# 3DR-APM25-Power-Module-V10.net
KiCad netlist of a schematic drawn in EAGLE
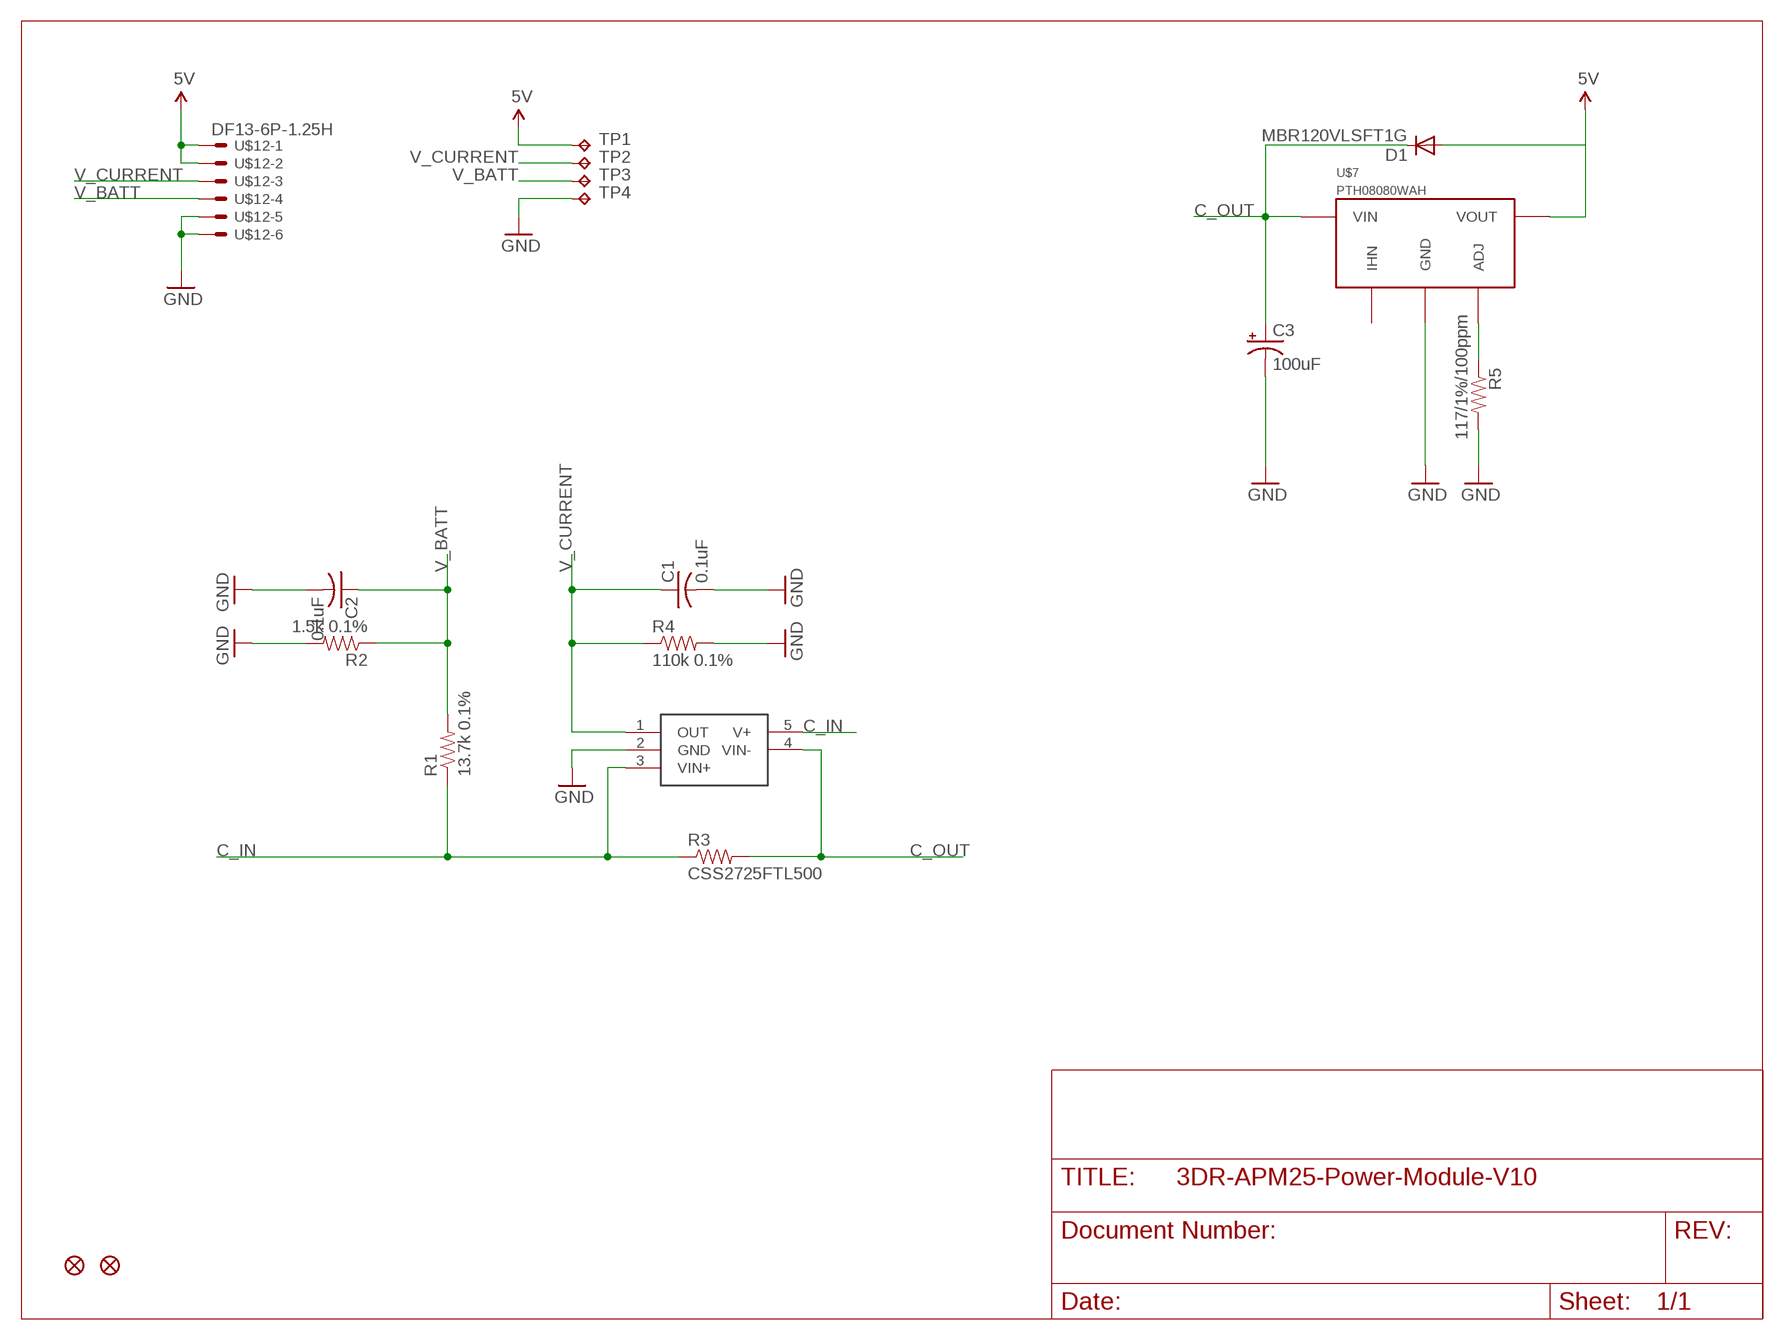
[diagram p0: schematic, sheet 1]

(export (version "E")
  (design (tool "Eeschema 10.0.6"))
  (components
    (comp (ref "C1")
      (value "0.1uF")
      (footprint "eagle-import:C0402")
      (libsource (lib "eagle-import") (part "C-USC0402"))
    )
    (comp (ref "C2")
      (value "0.1uF")
      (footprint "eagle-import:C0402")
      (libsource (lib "eagle-import") (part "C-USC0402"))
    )
    (comp (ref "C3")
      (value "100uF")
      (footprint "eagle-import:EIA7343")
      (libsource (lib "eagle-import") (part "CAP_POL7343"))
    )
    (comp (ref "D1")
      (value "MBR120VLSFT1G")
      (footprint "eagle-import:SOD-123-DIO")
      (libsource (lib "eagle-import") (part "DIODE-SOD-123"))
    )
    (comp (ref "JP1")
      (value "FIDUCIAL1X2")
      (footprint "eagle-import:FIDUCIAL-1X2")
      (libsource (lib "eagle-import") (part "FIDUCIAL1X2"))
    )
    (comp (ref "JP2")
      (value "FIDUCIAL1X2")
      (footprint "eagle-import:FIDUCIAL-1X2")
      (libsource (lib "eagle-import") (part "FIDUCIAL1X2"))
    )
    (comp (ref "R1")
      (value "13.7k 0.1%")
      (footprint "eagle-import:0402-RES")
      (libsource (lib "eagle-import") (part "RESISTOR0402-RES"))
    )
    (comp (ref "R2")
      (value "1.5k 0.1%")
      (footprint "eagle-import:0402-RES")
      (libsource (lib "eagle-import") (part "RESISTOR0402-RES"))
    )
    (comp (ref "R3")
      (value "CSS2725FTL500")
      (footprint "eagle-import:2725-RES")
      (libsource (lib "eagle-import") (part "CSS2725FTL250"))
    )
    (comp (ref "R4")
      (value "110k 0.1%")
      (footprint "eagle-import:0402-RES")
      (libsource (lib "eagle-import") (part "RESISTOR0402-RES"))
    )
    (comp (ref "R5")
      (value "117/1%/100ppm")
      (footprint "eagle-import:0402-RES")
      (libsource (lib "eagle-import") (part "RESISTOR0402-RES"))
    )
    (comp (ref "TP1")
      (value "TPTP19SQ")
      (footprint "eagle-import:TP19SQ")
      (libsource (lib "eagle-import") (part "TPTP19SQ"))
    )
    (comp (ref "TP2")
      (value "TPTP19SQ")
      (footprint "eagle-import:TP19SQ")
      (libsource (lib "eagle-import") (part "TPTP19SQ"))
    )
    (comp (ref "TP3")
      (value "TPTP19SQ")
      (footprint "eagle-import:TP19SQ")
      (libsource (lib "eagle-import") (part "TPTP19SQ"))
    )
    (comp (ref "TP4")
      (value "TPTP19SQ")
      (footprint "eagle-import:TP19SQ")
      (libsource (lib "eagle-import") (part "TPTP19SQ"))
    )
    (comp (ref "U$2")
      (value "INA169")
      (footprint "eagle-import:SOT23-5")
      (libsource (lib "eagle-import") (part "INA169"))
    )
    (comp (ref "U$7")
      (value "PTH08080WAH")
      (footprint "eagle-import:PTH08080W_TH")
      (libsource (lib "eagle-import") (part "PTH08080WAH"))
    )
    (comp (ref "U$12")
      (value "DF13-6P-1.25H")
      (footprint "eagle-import:DF13A-6P-1.25H")
      (libsource (lib "eagle-import") (part "DF13-6P-1.25?H"))
    )
  )
  (nets
    (net (code "1") (name "/C_IN") (class "Default")
      (node (ref "R1") (pin "1") (pinfunction "1_1") (pintype "passive"))
      (node (ref "R3") (pin "P$1") (pinfunction "1_P$1") (pintype "passive"))
      (node (ref "U$2") (pin "3") (pinfunction "VIN+_3") (pintype "bidirectional"))
      (node (ref "U$2") (pin "5") (pinfunction "V+_5") (pintype "bidirectional"))
    )
    (net (code "2") (name "/C_OUT") (class "Default")
      (node (ref "C3") (pin "A") (pinfunction "+_A") (pintype "passive"))
      (node (ref "D1") (pin "C") (pinfunction "C_C") (pintype "passive"))
      (node (ref "R3") (pin "P$2") (pinfunction "2_P$2") (pintype "passive"))
      (node (ref "U$2") (pin "4") (pinfunction "VIN-_4") (pintype "bidirectional"))
      (node (ref "U$7") (pin "1") (pinfunction "VIN_1") (pintype "power_in"))
    )
    (net (code "3") (name "/V_BATT") (class "Default")
      (node (ref "C2") (pin "1") (pinfunction "1_1") (pintype "passive"))
      (node (ref "R1") (pin "2") (pinfunction "2_2") (pintype "passive"))
      (node (ref "R2") (pin "1") (pinfunction "1_1") (pintype "passive"))
      (node (ref "TP3") (pin "TP") (pinfunction "TP_TP") (pintype "input"))
      (node (ref "U$12") (pin "4") (pinfunction "S_4") (pintype "passive"))
    )
    (net (code "4") (name "/V_CURRENT") (class "Default")
      (node (ref "C1") (pin "1") (pinfunction "1_1") (pintype "passive"))
      (node (ref "R4") (pin "1") (pinfunction "1_1") (pintype "passive"))
      (node (ref "TP2") (pin "TP") (pinfunction "TP_TP") (pintype "input"))
      (node (ref "U$12") (pin "3") (pinfunction "S_3") (pintype "passive"))
      (node (ref "U$2") (pin "1") (pinfunction "OUT_1") (pintype "bidirectional"))
    )
    (net (code "5") (name "5V") (class "Default")
      (node (ref "D1") (pin "A") (pinfunction "A_A") (pintype "passive"))
      (node (ref "TP1") (pin "TP") (pinfunction "TP_TP") (pintype "input"))
      (node (ref "U$12") (pin "1") (pinfunction "S_1") (pintype "passive"))
      (node (ref "U$12") (pin "2") (pinfunction "S_2") (pintype "passive"))
      (node (ref "U$7") (pin "3") (pinfunction "VOUT_3") (pintype "power_in"))
    )
    (net (code "6") (name "GND") (class "Default")
      (node (ref "C1") (pin "2") (pinfunction "2_2") (pintype "passive"))
      (node (ref "C2") (pin "2") (pinfunction "2_2") (pintype "passive"))
      (node (ref "C3") (pin "C") (pinfunction "-_C") (pintype "passive"))
      (node (ref "R2") (pin "2") (pinfunction "2_2") (pintype "passive"))
      (node (ref "R4") (pin "2") (pinfunction "2_2") (pintype "passive"))
      (node (ref "R5") (pin "2") (pinfunction "2_2") (pintype "passive"))
      (node (ref "TP4") (pin "TP") (pinfunction "TP_TP") (pintype "input"))
      (node (ref "U$12") (pin "5") (pinfunction "S_5") (pintype "passive"))
      (node (ref "U$12") (pin "6") (pinfunction "S_6") (pintype "passive"))
      (node (ref "U$2") (pin "2") (pinfunction "GND_2") (pintype "bidirectional"))
      (node (ref "U$7") (pin "2") (pinfunction "GND_2") (pintype "power_in"))
    )
    (net (code "7") (name "Net-(U$7-ADJ)") (class "Default")
      (node (ref "R5") (pin "1") (pinfunction "1_1") (pintype "passive"))
      (node (ref "U$7") (pin "4") (pinfunction "ADJ_4") (pintype "bidirectional"))
    )
    (net (code "8") (name "unconnected-(U$7-IHN-Pad5)") (class "Default")
      (node (ref "U$7") (pin "5") (pinfunction "IHN_5") (pintype "bidirectional"))
    )
  )
)
